# SCH_Moonshine_std_2026-02-17.net
KiCad netlist of a schematic drawn in EasyEDA
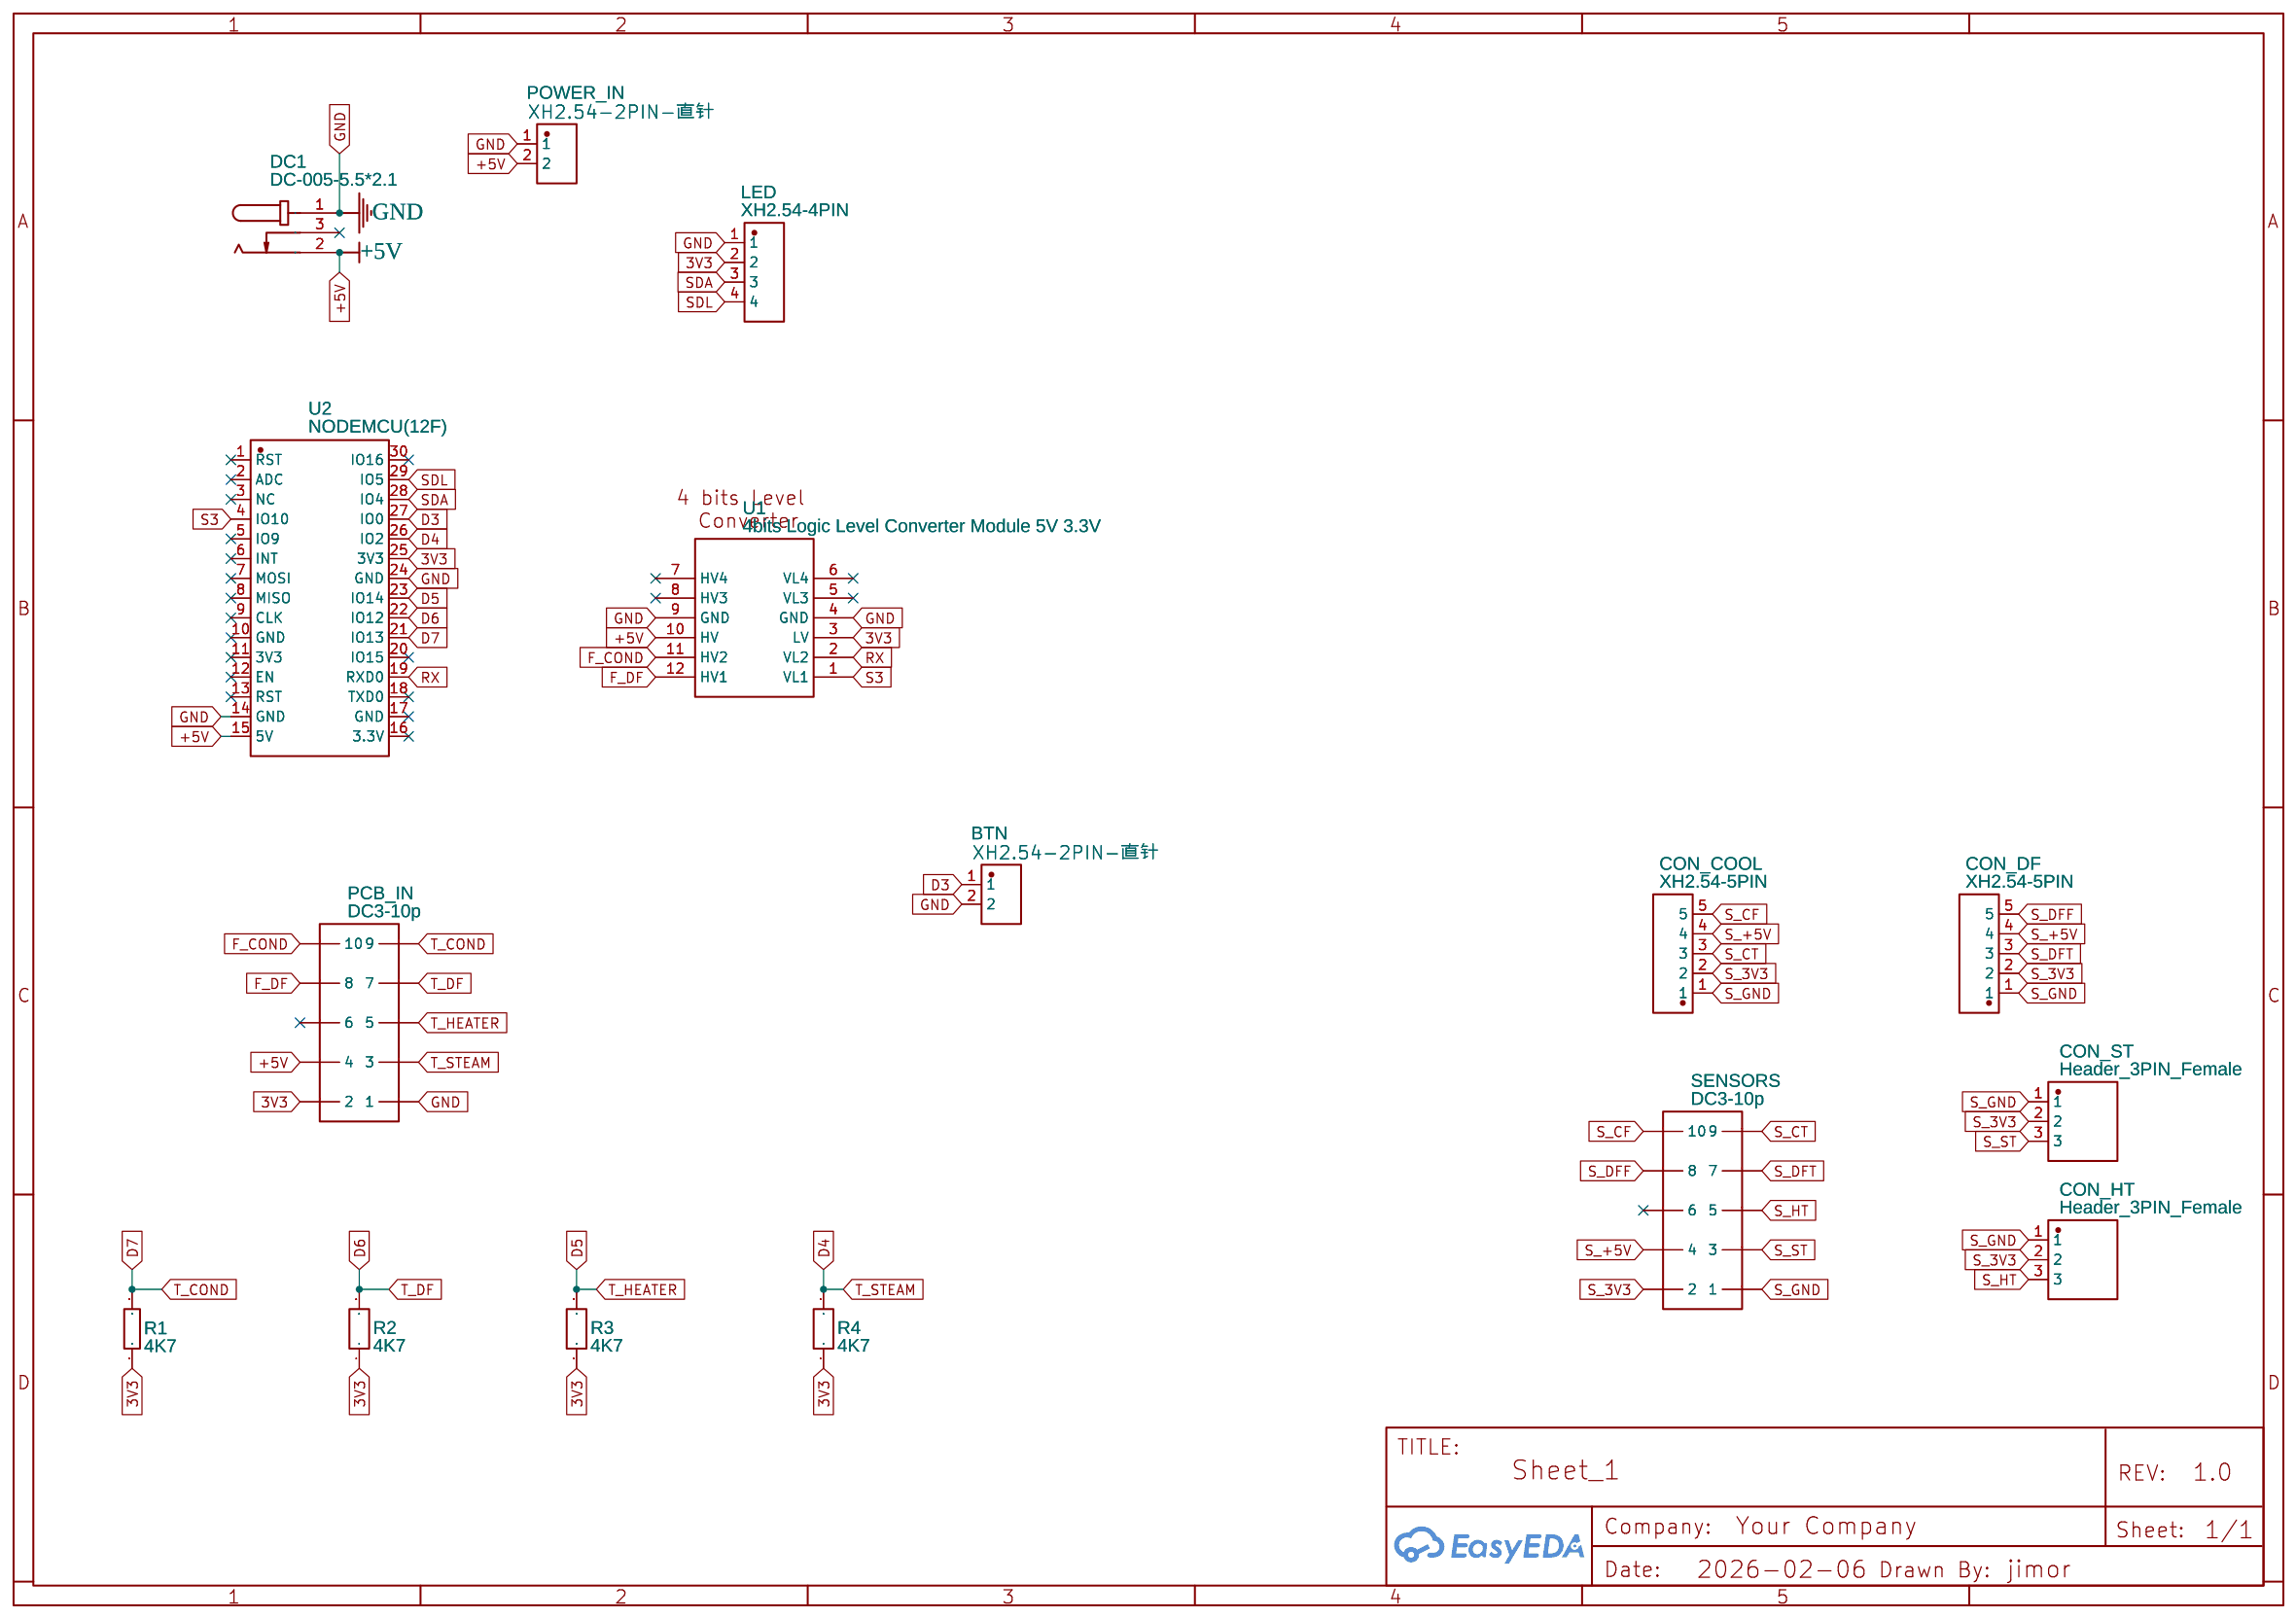
[diagram p0: schematic sheet]

(export (version "E")
  (design (tool "Eeschema 10.0.6"))
  (components
    (comp (ref "BTN") (value "XH2.54-2PIN-直针") (libsource (lib "") (part "XH2.54-2PIN-直针_1")))
    (comp (ref "CON_COOL")
      (value "XH2.54-5PIN")
      (fields (field (name "Manufacturer Part") "PZ254V-11-05P") (field (name "Manufacturer") "XFCN(兴飞)"))
      (libsource (lib "") (part "HDR-TH-2.54-1ROW-5PIN-39MIL-FRUITLOOP57"))
    )
    (comp (ref "CON_DF")
      (value "XH2.54-5PIN")
      (fields (field (name "Manufacturer Part") "PZ254V-11-05P") (field (name "Manufacturer") "XFCN(兴飞)"))
      (libsource (lib "") (part "HDR-TH-2.54-1ROW-5PIN-39MIL-FRUITLOOP57_1"))
    )
    (comp (ref "CON_HT")
      (value "Header_3PIN_Female")
      (fields (field (name "Manufacturer Part") "H123546") (field (name "Manufacturer") "MINTRON"))
      (libsource (lib "") (part "Header_3PIN_Female_1"))
    )
    (comp (ref "CON_ST")
      (value "Header_3PIN_Female")
      (fields (field (name "Manufacturer Part") "H123546") (field (name "Manufacturer") "MINTRON"))
      (libsource (lib "") (part "Header_3PIN_Female"))
    )
    (comp (ref "DC1") (value "DC-005-5.5*2.1") (libsource (lib "") (part "DC-005-5.5*2.1")))
    (comp (ref "LED") (value "XH2.54-4PIN") (libsource (lib "") (part "XH2.54-4PIN")))
    (comp (ref "PCB_IN") (value "DC3-10p") (libsource (lib "") (part "DC3-10p")))
    (comp (ref "POWER_IN") (value "XH2.54-2PIN-直针") (libsource (lib "") (part "XH2.54-2PIN-直针")))
    (comp (ref "R1")
      (value "4K7")
      (fields (field (name "Manufacturer Part") "AXIAL-0.4"))
      (libsource (lib "") (part "AXIAL-0.4"))
    )
    (comp (ref "R2")
      (value "4K7")
      (fields (field (name "Manufacturer Part") "3.3K-AXIAL-3.0") (field (name "Manufacturer") "睿思电阻"))
      (libsource (lib "") (part "3.3K-AXIAL-3.0"))
    )
    (comp (ref "R3")
      (value "4K7")
      (fields (field (name "Manufacturer Part") "3.3K-AXIAL-3.0") (field (name "Manufacturer") "睿思电阻"))
      (libsource (lib "") (part "3.3K-AXIAL-3.0"))
    )
    (comp (ref "R4")
      (value "4K7")
      (fields (field (name "Manufacturer Part") "3.3K-AXIAL-3.0") (field (name "Manufacturer") "睿思电阻"))
      (libsource (lib "") (part "3.3K-AXIAL-3.0"))
    )
    (comp (ref "SENSORS") (value "DC3-10p") (libsource (lib "") (part "DC3-10p_1")))
    (comp (ref "U1")
      (value "4bits Logic Level Converter Module 5V 3.3V")
      (libsource (lib "") (part "4bits Logic Level Converter Module 5V 3.3V"))
    )
    (comp (ref "U2")
      (value "NODEMCU(12F)")
      (fields (field (name "Manufacturer") "Ai-Thinker(安信可)"))
      (libsource (lib "") (part "NODEMCU(12F)"))
    )
  )
  (nets
    (net (code "1") (name "+5V") (class "Default")
      (node (ref "DC1") (pin "2") (pinfunction "2_2") (pintype "unspecified"))
      (node (ref "PCB_IN") (pin "4") (pinfunction "4_4") (pintype "unspecified"))
      (node (ref "POWER_IN") (pin "2") (pinfunction "2_2") (pintype "unspecified"))
      (node (ref "U1") (pin "10") (pinfunction "HV_10") (pintype "unspecified"))
      (node (ref "U2") (pin "15") (pinfunction "5V_15") (pintype "unspecified"))
    )
    (net (code "2") (name "3V3") (class "Default")
      (node (ref "LED") (pin "2") (pinfunction "2_2") (pintype "unspecified"))
      (node (ref "PCB_IN") (pin "2") (pinfunction "2_2") (pintype "unspecified"))
      (node (ref "R1") (pin "1") (pinfunction "1_1") (pintype "unspecified"))
      (node (ref "R2") (pin "1") (pinfunction "1_1") (pintype "unspecified"))
      (node (ref "R3") (pin "1") (pinfunction "1_1") (pintype "unspecified"))
      (node (ref "R4") (pin "1") (pinfunction "1_1") (pintype "unspecified"))
      (node (ref "U1") (pin "3") (pinfunction "LV_3") (pintype "unspecified"))
      (node (ref "U2") (pin "25") (pinfunction "3V3_25") (pintype "unspecified"))
    )
    (net (code "3") (name "D3") (class "Default")
      (node (ref "BTN") (pin "1") (pinfunction "1_1") (pintype "unspecified"))
      (node (ref "U2") (pin "27") (pinfunction "IO0_27") (pintype "unspecified"))
    )
    (net (code "4") (name "D4") (class "Default")
      (node (ref "PCB_IN") (pin "3") (pinfunction "3_3") (pintype "unspecified"))
      (node (ref "R4") (pin "2") (pinfunction "2_2") (pintype "unspecified"))
      (node (ref "U2") (pin "26") (pinfunction "IO2_26") (pintype "unspecified"))
    )
    (net (code "5") (name "D5") (class "Default")
      (node (ref "PCB_IN") (pin "5") (pinfunction "5_5") (pintype "unspecified"))
      (node (ref "R3") (pin "2") (pinfunction "2_2") (pintype "unspecified"))
      (node (ref "U2") (pin "23") (pinfunction "IO14_23") (pintype "unspecified"))
    )
    (net (code "6") (name "D6") (class "Default")
      (node (ref "PCB_IN") (pin "7") (pinfunction "7_7") (pintype "unspecified"))
      (node (ref "R2") (pin "2") (pinfunction "2_2") (pintype "unspecified"))
      (node (ref "U2") (pin "22") (pinfunction "IO12_22") (pintype "unspecified"))
    )
    (net (code "7") (name "D7") (class "Default")
      (node (ref "PCB_IN") (pin "9") (pinfunction "9_9") (pintype "unspecified"))
      (node (ref "R1") (pin "2") (pinfunction "2_2") (pintype "unspecified"))
      (node (ref "U2") (pin "21") (pinfunction "IO13_21") (pintype "unspecified"))
    )
    (net (code "8") (name "F_COND") (class "Default")
      (node (ref "PCB_IN") (pin "10") (pinfunction "10_10") (pintype "unspecified"))
      (node (ref "U1") (pin "11") (pinfunction "HV2_11") (pintype "unspecified"))
    )
    (net (code "9") (name "F_DF") (class "Default")
      (node (ref "PCB_IN") (pin "8") (pinfunction "8_8") (pintype "unspecified"))
      (node (ref "U1") (pin "12") (pinfunction "HV1_12") (pintype "unspecified"))
    )
    (net (code "10") (name "GND") (class "Default")
      (node (ref "BTN") (pin "2") (pinfunction "2_2") (pintype "unspecified"))
      (node (ref "DC1") (pin "1") (pinfunction "1_1") (pintype "unspecified"))
      (node (ref "LED") (pin "1") (pinfunction "1_1") (pintype "unspecified"))
      (node (ref "PCB_IN") (pin "1") (pinfunction "1_1") (pintype "unspecified"))
      (node (ref "POWER_IN") (pin "1") (pinfunction "1_1") (pintype "unspecified"))
      (node (ref "U1") (pin "4") (pinfunction "GND_4") (pintype "unspecified"))
      (node (ref "U1") (pin "9") (pinfunction "GND_9") (pintype "unspecified"))
      (node (ref "U2") (pin "14") (pinfunction "GND_14") (pintype "unspecified"))
      (node (ref "U2") (pin "24") (pinfunction "GND_24") (pintype "unspecified"))
    )
    (net (code "11") (name "RX") (class "Default")
      (node (ref "U1") (pin "2") (pinfunction "VL2_2") (pintype "unspecified"))
      (node (ref "U2") (pin "19") (pinfunction "RXD0_19") (pintype "unspecified"))
    )
    (net (code "12") (name "S3") (class "Default")
      (node (ref "U1") (pin "1") (pinfunction "VL1_1") (pintype "unspecified"))
      (node (ref "U2") (pin "4") (pinfunction "IO10_4") (pintype "unspecified"))
    )
    (net (code "13") (name "SDA") (class "Default")
      (node (ref "LED") (pin "3") (pinfunction "3_3") (pintype "unspecified"))
      (node (ref "U2") (pin "28") (pinfunction "IO4_28") (pintype "unspecified"))
    )
    (net (code "14") (name "SDL") (class "Default")
      (node (ref "LED") (pin "4") (pinfunction "4_4") (pintype "unspecified"))
      (node (ref "U2") (pin "29") (pinfunction "IO5_29") (pintype "unspecified"))
    )
    (net (code "15") (name "S_+5V") (class "Default")
      (node (ref "CON_COOL") (pin "4") (pinfunction "4_4") (pintype "unspecified"))
      (node (ref "CON_DF") (pin "4") (pinfunction "4_4") (pintype "unspecified"))
      (node (ref "SENSORS") (pin "4") (pinfunction "4_4") (pintype "unspecified"))
    )
    (net (code "16") (name "S_3V3") (class "Default")
      (node (ref "CON_COOL") (pin "2") (pinfunction "2_2") (pintype "unspecified"))
      (node (ref "CON_DF") (pin "2") (pinfunction "2_2") (pintype "unspecified"))
      (node (ref "CON_HT") (pin "2") (pinfunction "2_2") (pintype "unspecified"))
      (node (ref "CON_ST") (pin "2") (pinfunction "2_2") (pintype "unspecified"))
      (node (ref "SENSORS") (pin "2") (pinfunction "2_2") (pintype "unspecified"))
    )
    (net (code "17") (name "S_CF") (class "Default")
      (node (ref "CON_COOL") (pin "5") (pinfunction "5_5") (pintype "unspecified"))
      (node (ref "SENSORS") (pin "10") (pinfunction "10_10") (pintype "unspecified"))
    )
    (net (code "18") (name "S_CT") (class "Default")
      (node (ref "CON_COOL") (pin "3") (pinfunction "3_3") (pintype "unspecified"))
      (node (ref "SENSORS") (pin "9") (pinfunction "9_9") (pintype "unspecified"))
    )
    (net (code "19") (name "S_DFF") (class "Default")
      (node (ref "CON_DF") (pin "5") (pinfunction "5_5") (pintype "unspecified"))
      (node (ref "SENSORS") (pin "8") (pinfunction "8_8") (pintype "unspecified"))
    )
    (net (code "20") (name "S_DFT") (class "Default")
      (node (ref "CON_DF") (pin "3") (pinfunction "3_3") (pintype "unspecified"))
      (node (ref "SENSORS") (pin "7") (pinfunction "7_7") (pintype "unspecified"))
    )
    (net (code "21") (name "S_GND") (class "Default")
      (node (ref "CON_COOL") (pin "1") (pinfunction "1_1") (pintype "unspecified"))
      (node (ref "CON_DF") (pin "1") (pinfunction "1_1") (pintype "unspecified"))
      (node (ref "CON_HT") (pin "1") (pinfunction "1_1") (pintype "unspecified"))
      (node (ref "CON_ST") (pin "1") (pinfunction "1_1") (pintype "unspecified"))
      (node (ref "SENSORS") (pin "1") (pinfunction "1_1") (pintype "unspecified"))
    )
    (net (code "22") (name "S_HT") (class "Default")
      (node (ref "CON_HT") (pin "3") (pinfunction "3_3") (pintype "unspecified"))
      (node (ref "SENSORS") (pin "5") (pinfunction "5_5") (pintype "unspecified"))
    )
    (net (code "23") (name "S_ST") (class "Default")
      (node (ref "CON_ST") (pin "3") (pinfunction "3_3") (pintype "unspecified"))
      (node (ref "SENSORS") (pin "3") (pinfunction "3_3") (pintype "unspecified"))
    )
    (net (code "24") (name "unconnected-(DC1-Pad3)") (class "Default")
      (node (ref "DC1") (pin "3") (pinfunction "3_3") (pintype "unspecified+no_connect"))
    )
    (net (code "25") (name "unconnected-(PCB_IN-Pad6)") (class "Default")
      (node (ref "PCB_IN") (pin "6") (pinfunction "6_6") (pintype "unspecified+no_connect"))
    )
    (net (code "26") (name "unconnected-(SENSORS-Pad6)") (class "Default")
      (node (ref "SENSORS") (pin "6") (pinfunction "6_6") (pintype "unspecified+no_connect"))
    )
    (net (code "27") (name "unconnected-(U1-HV3-Pad8)") (class "Default")
      (node (ref "U1") (pin "8") (pinfunction "HV3_8") (pintype "unspecified+no_connect"))
    )
    (net (code "28") (name "unconnected-(U1-HV4-Pad7)") (class "Default")
      (node (ref "U1") (pin "7") (pinfunction "HV4_7") (pintype "unspecified+no_connect"))
    )
    (net (code "29") (name "unconnected-(U1-VL3-Pad5)") (class "Default")
      (node (ref "U1") (pin "5") (pinfunction "VL3_5") (pintype "unspecified+no_connect"))
    )
    (net (code "30") (name "unconnected-(U1-VL4-Pad6)") (class "Default")
      (node (ref "U1") (pin "6") (pinfunction "VL4_6") (pintype "unspecified+no_connect"))
    )
    (net (code "31") (name "unconnected-(U2-3.3V-Pad16)") (class "Default")
      (node (ref "U2") (pin "16") (pinfunction "3.3V_16") (pintype "unspecified+no_connect"))
    )
    (net (code "32") (name "unconnected-(U2-3V3-Pad11)") (class "Default")
      (node (ref "U2") (pin "11") (pinfunction "3V3_11") (pintype "unspecified+no_connect"))
    )
    (net (code "33") (name "unconnected-(U2-ADC-Pad2)") (class "Default")
      (node (ref "U2") (pin "2") (pinfunction "ADC_2") (pintype "unspecified+no_connect"))
    )
    (net (code "34") (name "unconnected-(U2-CLK-Pad9)") (class "Default")
      (node (ref "U2") (pin "9") (pinfunction "CLK_9") (pintype "unspecified+no_connect"))
    )
    (net (code "35") (name "unconnected-(U2-EN-Pad12)") (class "Default")
      (node (ref "U2") (pin "12") (pinfunction "EN_12") (pintype "unspecified+no_connect"))
    )
    (net (code "36") (name "unconnected-(U2-GND-Pad10)") (class "Default")
      (node (ref "U2") (pin "10") (pinfunction "GND_10") (pintype "unspecified+no_connect"))
    )
    (net (code "37") (name "unconnected-(U2-GND-Pad17)") (class "Default")
      (node (ref "U2") (pin "17") (pinfunction "GND_17") (pintype "unspecified+no_connect"))
    )
    (net (code "38") (name "unconnected-(U2-INT-Pad6)") (class "Default")
      (node (ref "U2") (pin "6") (pinfunction "INT_6") (pintype "unspecified+no_connect"))
    )
    (net (code "39") (name "unconnected-(U2-IO9-Pad5)") (class "Default")
      (node (ref "U2") (pin "5") (pinfunction "IO9_5") (pintype "unspecified+no_connect"))
    )
    (net (code "40") (name "unconnected-(U2-IO15-Pad20)") (class "Default")
      (node (ref "U2") (pin "20") (pinfunction "IO15_20") (pintype "unspecified+no_connect"))
    )
    (net (code "41") (name "unconnected-(U2-IO16-Pad30)") (class "Default")
      (node (ref "U2") (pin "30") (pinfunction "IO16_30") (pintype "unspecified+no_connect"))
    )
    (net (code "42") (name "unconnected-(U2-MISO-Pad8)") (class "Default")
      (node (ref "U2") (pin "8") (pinfunction "MISO_8") (pintype "unspecified+no_connect"))
    )
    (net (code "43") (name "unconnected-(U2-MOSI-Pad7)") (class "Default")
      (node (ref "U2") (pin "7") (pinfunction "MOSI_7") (pintype "unspecified+no_connect"))
    )
    (net (code "44") (name "unconnected-(U2-NC-Pad3)") (class "Default")
      (node (ref "U2") (pin "3") (pinfunction "NC_3") (pintype "unspecified+no_connect"))
    )
    (net (code "45") (name "unconnected-(U2-RST-Pad1)") (class "Default")
      (node (ref "U2") (pin "1") (pinfunction "RST_1") (pintype "unspecified+no_connect"))
    )
    (net (code "46") (name "unconnected-(U2-RST-Pad13)") (class "Default")
      (node (ref "U2") (pin "13") (pinfunction "RST_13") (pintype "unspecified+no_connect"))
    )
    (net (code "47") (name "unconnected-(U2-TXD0-Pad18)") (class "Default")
      (node (ref "U2") (pin "18") (pinfunction "TXD0_18") (pintype "unspecified+no_connect"))
    )
  )
)
